# plata_verhn.net
KiCad netlist of a schematic drawn in Altium Designer
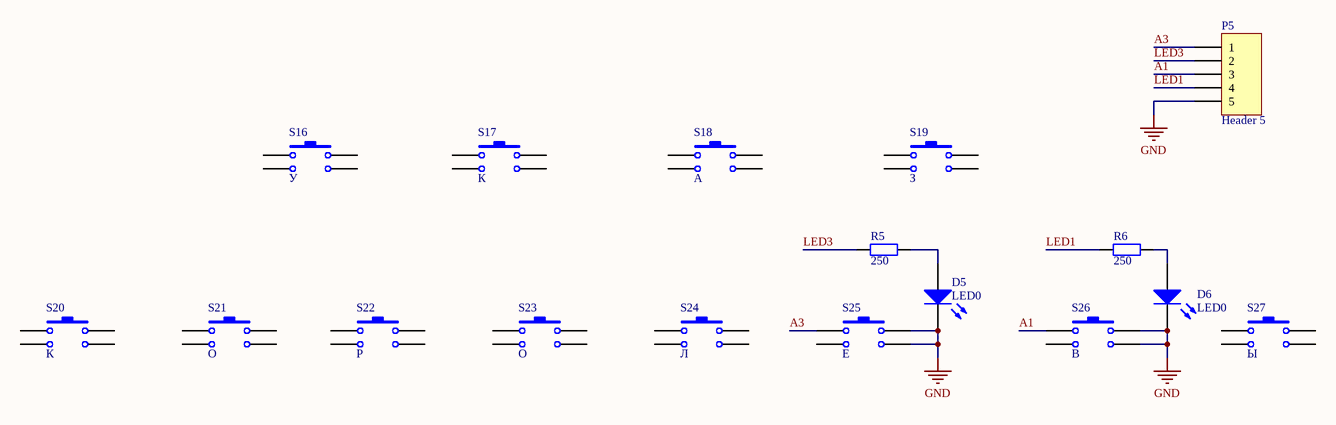
[diagram p0: plata_verhn.SchDoc]

(export (version "E")
  (design (tool "Eeschema 10.0.6"))
  (components
    (comp (ref "D5")
      (value "LED0")
      (footprint "LED0805")
      (description "Typical INFRARED GaAs LED")
      (fields (field (name "PUBLISHER") "Altium Limited"))
      (libsource (lib "Library") (part "LED0"))
    )
    (comp (ref "D6")
      (value "LED0")
      (footprint "LED0805")
      (description "Typical INFRARED GaAs LED")
      (fields (field (name "PUBLISHER") "Altium Limited"))
      (libsource (lib "Library") (part "LED0"))
    )
    (comp (ref "P5")
      (value "Header 5")
      (footprint "HDR1X5")
      (description "Header, 5-Pin")
      (fields (field (name "PUBLISHER") "Altium Limited"))
      (libsource (lib "Miscellaneous Connectors") (part "Header 5"))
    )
    (comp (ref "R5")
      (value "250")
      (footprint "6-0805_N")
      (description "Resistor")
      (fields (field (name "PUBLISHER") "Altium Limited"))
      (libsource (lib "Library") (part "Res2"))
    )
    (comp (ref "R6")
      (value "250")
      (footprint "6-0805_N")
      (description "Resistor")
      (fields (field (name "PUBLISHER") "Altium Limited"))
      (libsource (lib "Library") (part "Res2"))
    )
    (comp (ref "S16")
      (value "У")
      (footprint "STMW")
      (description "Switch")
      (fields (field (name "PUBLISHER") "Altium Limited"))
      (libsource (lib "Library") (part "STMW"))
    )
    (comp (ref "S17")
      (value "К")
      (footprint "STMW")
      (description "Switch")
      (fields (field (name "PUBLISHER") "Altium Limited"))
      (libsource (lib "Library") (part "STMW"))
    )
    (comp (ref "S18")
      (value "А")
      (footprint "STMW")
      (description "Switch")
      (fields (field (name "PUBLISHER") "Altium Limited"))
      (libsource (lib "Library") (part "STMW"))
    )
    (comp (ref "S19")
      (value "З")
      (footprint "STMW")
      (description "Switch")
      (fields (field (name "PUBLISHER") "Altium Limited"))
      (libsource (lib "Library") (part "STMW"))
    )
    (comp (ref "S20")
      (value "К")
      (footprint "STMW")
      (description "Switch")
      (fields (field (name "PUBLISHER") "Altium Limited"))
      (libsource (lib "Library") (part "STMW"))
    )
    (comp (ref "S21")
      (value "О")
      (footprint "STMW")
      (description "Switch")
      (fields (field (name "PUBLISHER") "Altium Limited"))
      (libsource (lib "Library") (part "STMW"))
    )
    (comp (ref "S22")
      (value "Р")
      (footprint "STMW")
      (description "Switch")
      (fields (field (name "PUBLISHER") "Altium Limited"))
      (libsource (lib "Library") (part "STMW"))
    )
    (comp (ref "S23")
      (value "О")
      (footprint "STMW")
      (description "Switch")
      (fields (field (name "PUBLISHER") "Altium Limited"))
      (libsource (lib "Library") (part "STMW"))
    )
    (comp (ref "S24")
      (value "Л")
      (footprint "STMW")
      (description "Switch")
      (fields (field (name "PUBLISHER") "Altium Limited"))
      (libsource (lib "Library") (part "STMW"))
    )
    (comp (ref "S25")
      (value "Е")
      (footprint "STMW")
      (description "Switch")
      (fields (field (name "PUBLISHER") "Altium Limited"))
      (libsource (lib "Library") (part "STMW"))
    )
    (comp (ref "S26")
      (value "В")
      (footprint "STMW")
      (description "Switch")
      (fields (field (name "PUBLISHER") "Altium Limited"))
      (libsource (lib "Library") (part "STMW"))
    )
    (comp (ref "S27")
      (value "Ы")
      (footprint "STMW")
      (description "Switch")
      (fields (field (name "PUBLISHER") "Altium Limited"))
      (libsource (lib "Library") (part "STMW"))
    )
  )
  (nets
    (net (code "1") (name "/A1") (class "Default")
      (node (ref "P5") (pin "3") (pinfunction "3_3") (pintype "passive"))
      (node (ref "S26") (pin "1") (pinfunction "1_1") (pintype "passive"))
    )
    (net (code "2") (name "/A3") (class "Default")
      (node (ref "P5") (pin "1") (pinfunction "1_1") (pintype "passive"))
      (node (ref "S25") (pin "1") (pinfunction "1_1") (pintype "passive"))
    )
    (net (code "3") (name "/LED1") (class "Default")
      (node (ref "P5") (pin "4") (pinfunction "4_4") (pintype "passive"))
      (node (ref "R6") (pin "2") (pinfunction "2_2") (pintype "passive"))
    )
    (net (code "4") (name "/LED3") (class "Default")
      (node (ref "P5") (pin "2") (pinfunction "2_2") (pintype "passive"))
      (node (ref "R5") (pin "2") (pinfunction "2_2") (pintype "passive"))
    )
    (net (code "5") (name "GND") (class "Default")
      (node (ref "D5") (pin "2") (pinfunction "K_2") (pintype "passive"))
      (node (ref "D6") (pin "2") (pinfunction "K_2") (pintype "passive"))
      (node (ref "P5") (pin "5") (pinfunction "5_5") (pintype "passive"))
      (node (ref "S25") (pin "2") (pinfunction "2_2") (pintype "passive"))
      (node (ref "S26") (pin "2") (pinfunction "2_2") (pintype "passive"))
    )
    (net (code "6") (name "Net-(D5-A)") (class "Default")
      (node (ref "D5") (pin "1") (pinfunction "A_1") (pintype "passive"))
      (node (ref "R5") (pin "1") (pinfunction "1_1") (pintype "passive"))
    )
    (net (code "7") (name "Net-(D6-A)") (class "Default")
      (node (ref "D6") (pin "1") (pinfunction "A_1") (pintype "passive"))
      (node (ref "R6") (pin "1") (pinfunction "1_1") (pintype "passive"))
    )
    (net (code "8") (name "unconnected-(S16-Pad1)") (class "Default")
      (node (ref "S16") (pin "1") (pinfunction "1_1") (pintype "passive"))
    )
    (net (code "9") (name "unconnected-(S16-Pad1)_1") (class "Default")
      (node (ref "S16") (pin "1") (pinfunction "1_1") (pintype "passive"))
    )
    (net (code "10") (name "unconnected-(S16-Pad2)") (class "Default")
      (node (ref "S16") (pin "2") (pinfunction "2_2") (pintype "passive"))
    )
    (net (code "11") (name "unconnected-(S16-Pad2)_1") (class "Default")
      (node (ref "S16") (pin "2") (pinfunction "2_2") (pintype "passive"))
    )
    (net (code "12") (name "unconnected-(S17-Pad1)") (class "Default")
      (node (ref "S17") (pin "1") (pinfunction "1_1") (pintype "passive"))
    )
    (net (code "13") (name "unconnected-(S17-Pad1)_1") (class "Default")
      (node (ref "S17") (pin "1") (pinfunction "1_1") (pintype "passive"))
    )
    (net (code "14") (name "unconnected-(S17-Pad2)") (class "Default")
      (node (ref "S17") (pin "2") (pinfunction "2_2") (pintype "passive"))
    )
    (net (code "15") (name "unconnected-(S17-Pad2)_1") (class "Default")
      (node (ref "S17") (pin "2") (pinfunction "2_2") (pintype "passive"))
    )
    (net (code "16") (name "unconnected-(S18-Pad1)") (class "Default")
      (node (ref "S18") (pin "1") (pinfunction "1_1") (pintype "passive"))
    )
    (net (code "17") (name "unconnected-(S18-Pad1)_1") (class "Default")
      (node (ref "S18") (pin "1") (pinfunction "1_1") (pintype "passive"))
    )
    (net (code "18") (name "unconnected-(S18-Pad2)") (class "Default")
      (node (ref "S18") (pin "2") (pinfunction "2_2") (pintype "passive"))
    )
    (net (code "19") (name "unconnected-(S18-Pad2)_1") (class "Default")
      (node (ref "S18") (pin "2") (pinfunction "2_2") (pintype "passive"))
    )
    (net (code "20") (name "unconnected-(S19-Pad1)") (class "Default")
      (node (ref "S19") (pin "1") (pinfunction "1_1") (pintype "passive"))
    )
    (net (code "21") (name "unconnected-(S19-Pad1)_1") (class "Default")
      (node (ref "S19") (pin "1") (pinfunction "1_1") (pintype "passive"))
    )
    (net (code "22") (name "unconnected-(S19-Pad2)") (class "Default")
      (node (ref "S19") (pin "2") (pinfunction "2_2") (pintype "passive"))
    )
    (net (code "23") (name "unconnected-(S19-Pad2)_1") (class "Default")
      (node (ref "S19") (pin "2") (pinfunction "2_2") (pintype "passive"))
    )
    (net (code "24") (name "unconnected-(S20-Pad1)") (class "Default")
      (node (ref "S20") (pin "1") (pinfunction "1_1") (pintype "passive"))
    )
    (net (code "25") (name "unconnected-(S20-Pad1)_1") (class "Default")
      (node (ref "S20") (pin "1") (pinfunction "1_1") (pintype "passive"))
    )
    (net (code "26") (name "unconnected-(S20-Pad2)") (class "Default")
      (node (ref "S20") (pin "2") (pinfunction "2_2") (pintype "passive"))
    )
    (net (code "27") (name "unconnected-(S20-Pad2)_1") (class "Default")
      (node (ref "S20") (pin "2") (pinfunction "2_2") (pintype "passive"))
    )
    (net (code "28") (name "unconnected-(S21-Pad1)") (class "Default")
      (node (ref "S21") (pin "1") (pinfunction "1_1") (pintype "passive"))
    )
    (net (code "29") (name "unconnected-(S21-Pad1)_1") (class "Default")
      (node (ref "S21") (pin "1") (pinfunction "1_1") (pintype "passive"))
    )
    (net (code "30") (name "unconnected-(S21-Pad2)") (class "Default")
      (node (ref "S21") (pin "2") (pinfunction "2_2") (pintype "passive"))
    )
    (net (code "31") (name "unconnected-(S21-Pad2)_1") (class "Default")
      (node (ref "S21") (pin "2") (pinfunction "2_2") (pintype "passive"))
    )
    (net (code "32") (name "unconnected-(S22-Pad1)") (class "Default")
      (node (ref "S22") (pin "1") (pinfunction "1_1") (pintype "passive"))
    )
    (net (code "33") (name "unconnected-(S22-Pad1)_1") (class "Default")
      (node (ref "S22") (pin "1") (pinfunction "1_1") (pintype "passive"))
    )
    (net (code "34") (name "unconnected-(S22-Pad2)") (class "Default")
      (node (ref "S22") (pin "2") (pinfunction "2_2") (pintype "passive"))
    )
    (net (code "35") (name "unconnected-(S22-Pad2)_1") (class "Default")
      (node (ref "S22") (pin "2") (pinfunction "2_2") (pintype "passive"))
    )
    (net (code "36") (name "unconnected-(S23-Pad1)") (class "Default")
      (node (ref "S23") (pin "1") (pinfunction "1_1") (pintype "passive"))
    )
    (net (code "37") (name "unconnected-(S23-Pad1)_1") (class "Default")
      (node (ref "S23") (pin "1") (pinfunction "1_1") (pintype "passive"))
    )
    (net (code "38") (name "unconnected-(S23-Pad2)") (class "Default")
      (node (ref "S23") (pin "2") (pinfunction "2_2") (pintype "passive"))
    )
    (net (code "39") (name "unconnected-(S23-Pad2)_1") (class "Default")
      (node (ref "S23") (pin "2") (pinfunction "2_2") (pintype "passive"))
    )
    (net (code "40") (name "unconnected-(S24-Pad1)") (class "Default")
      (node (ref "S24") (pin "1") (pinfunction "1_1") (pintype "passive"))
    )
    (net (code "41") (name "unconnected-(S24-Pad1)_1") (class "Default")
      (node (ref "S24") (pin "1") (pinfunction "1_1") (pintype "passive"))
    )
    (net (code "42") (name "unconnected-(S24-Pad2)") (class "Default")
      (node (ref "S24") (pin "2") (pinfunction "2_2") (pintype "passive"))
    )
    (net (code "43") (name "unconnected-(S24-Pad2)_1") (class "Default")
      (node (ref "S24") (pin "2") (pinfunction "2_2") (pintype "passive"))
    )
    (net (code "44") (name "unconnected-(S25-Pad1)") (class "Default")
      (node (ref "S25") (pin "1") (pinfunction "1_1") (pintype "passive"))
    )
    (net (code "45") (name "unconnected-(S26-Pad1)") (class "Default")
      (node (ref "S26") (pin "1") (pinfunction "1_1") (pintype "passive"))
    )
    (net (code "46") (name "unconnected-(S27-Pad1)") (class "Default")
      (node (ref "S27") (pin "1") (pinfunction "1_1") (pintype "passive"))
    )
    (net (code "47") (name "unconnected-(S27-Pad1)_1") (class "Default")
      (node (ref "S27") (pin "1") (pinfunction "1_1") (pintype "passive"))
    )
    (net (code "48") (name "unconnected-(S27-Pad2)") (class "Default")
      (node (ref "S27") (pin "2") (pinfunction "2_2") (pintype "passive"))
    )
    (net (code "49") (name "unconnected-(S27-Pad2)_1") (class "Default")
      (node (ref "S27") (pin "2") (pinfunction "2_2") (pintype "passive"))
    )
  )
)
